# center_pcb.net
KiCad netlist of a schematic drawn in EAGLE
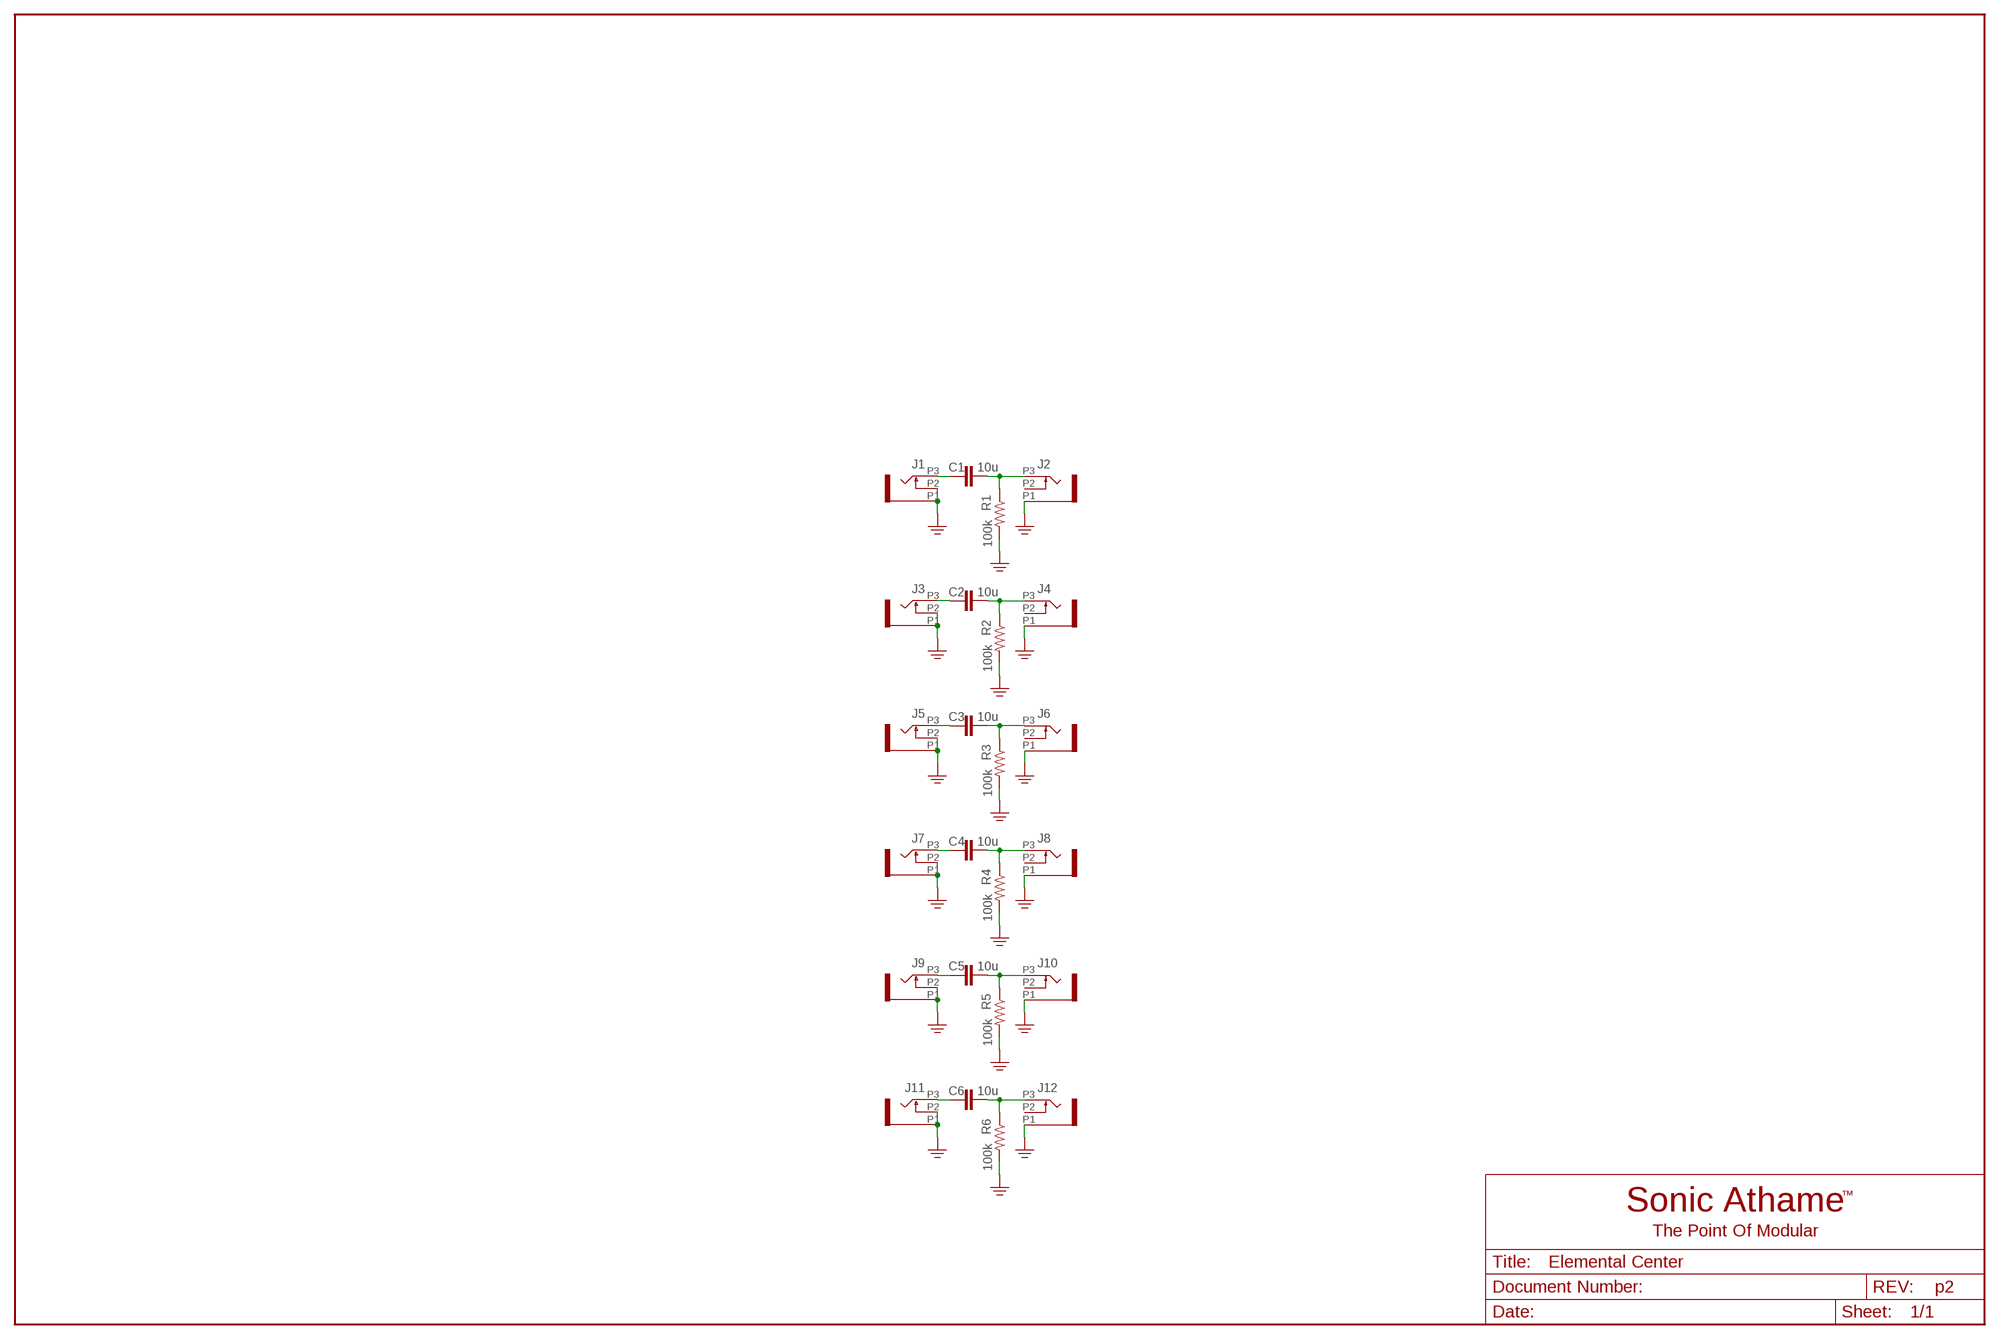
[diagram p0: schematic, sheet 1]

(export (version "E")
  (design (tool "Eeschema 10.0.6"))
  (components
    (comp (ref "C1")
      (value "10u")
      (footprint "eagle-import:C025-024X044")
      (libsource (lib "eagle-import") (part "CAP_NONPOL025-024X044"))
    )
    (comp (ref "C2")
      (value "10u")
      (footprint "eagle-import:C025-024X044")
      (libsource (lib "eagle-import") (part "CAP_NONPOL025-024X044"))
    )
    (comp (ref "C3")
      (value "10u")
      (footprint "eagle-import:C025-024X044")
      (libsource (lib "eagle-import") (part "CAP_NONPOL025-024X044"))
    )
    (comp (ref "C4")
      (value "10u")
      (footprint "eagle-import:C025-024X044")
      (libsource (lib "eagle-import") (part "CAP_NONPOL025-024X044"))
    )
    (comp (ref "C5")
      (value "10u")
      (footprint "eagle-import:C025-024X044")
      (libsource (lib "eagle-import") (part "CAP_NONPOL025-024X044"))
    )
    (comp (ref "C6")
      (value "10u")
      (footprint "eagle-import:C025-024X044")
      (libsource (lib "eagle-import") (part "CAP_NONPOL025-024X044"))
    )
    (comp (ref "J1")
      (value "WQP-PJ398SM6")
      (footprint "eagle-import:WQP_PJ_301M6")
      (libsource (lib "eagle-import") (part "WQP-PJ398SM6"))
    )
    (comp (ref "J2")
      (value "WQP-PJ398SM6")
      (footprint "eagle-import:WQP_PJ_301M6")
      (libsource (lib "eagle-import") (part "WQP-PJ398SM6"))
    )
    (comp (ref "J3")
      (value "WQP-PJ398SM6")
      (footprint "eagle-import:WQP_PJ_301M6")
      (libsource (lib "eagle-import") (part "WQP-PJ398SM6"))
    )
    (comp (ref "J4")
      (value "WQP-PJ398SM6")
      (footprint "eagle-import:WQP_PJ_301M6")
      (libsource (lib "eagle-import") (part "WQP-PJ398SM6"))
    )
    (comp (ref "J5")
      (value "WQP-PJ398SM6")
      (footprint "eagle-import:WQP_PJ_301M6")
      (libsource (lib "eagle-import") (part "WQP-PJ398SM6"))
    )
    (comp (ref "J6")
      (value "WQP-PJ398SM6")
      (footprint "eagle-import:WQP_PJ_301M6")
      (libsource (lib "eagle-import") (part "WQP-PJ398SM6"))
    )
    (comp (ref "J7")
      (value "WQP-PJ398SM6")
      (footprint "eagle-import:WQP_PJ_301M6")
      (libsource (lib "eagle-import") (part "WQP-PJ398SM6"))
    )
    (comp (ref "J8")
      (value "WQP-PJ398SM6")
      (footprint "eagle-import:WQP_PJ_301M6")
      (libsource (lib "eagle-import") (part "WQP-PJ398SM6"))
    )
    (comp (ref "J9")
      (value "WQP-PJ398SM6")
      (footprint "eagle-import:WQP_PJ_301M6")
      (libsource (lib "eagle-import") (part "WQP-PJ398SM6"))
    )
    (comp (ref "J10")
      (value "WQP-PJ398SM6")
      (footprint "eagle-import:WQP_PJ_301M6")
      (libsource (lib "eagle-import") (part "WQP-PJ398SM6"))
    )
    (comp (ref "J11")
      (value "WQP-PJ398SM6")
      (footprint "eagle-import:WQP_PJ_301M6")
      (libsource (lib "eagle-import") (part "WQP-PJ398SM6"))
    )
    (comp (ref "J12")
      (value "WQP-PJ398SM6")
      (footprint "eagle-import:WQP_PJ_301M6")
      (libsource (lib "eagle-import") (part "WQP-PJ398SM6"))
    )
    (comp (ref "R1")
      (value "100k")
      (footprint "eagle-import:0207_2V")
      (libsource (lib "eagle-import") (part "RESISTOR0207/2V"))
    )
    (comp (ref "R2")
      (value "100k")
      (footprint "eagle-import:0207_2V")
      (libsource (lib "eagle-import") (part "RESISTOR0207/2V"))
    )
    (comp (ref "R3")
      (value "100k")
      (footprint "eagle-import:0207_2V")
      (libsource (lib "eagle-import") (part "RESISTOR0207/2V"))
    )
    (comp (ref "R4")
      (value "100k")
      (footprint "eagle-import:0207_2V")
      (libsource (lib "eagle-import") (part "RESISTOR0207/2V"))
    )
    (comp (ref "R5")
      (value "100k")
      (footprint "eagle-import:0207_2V")
      (libsource (lib "eagle-import") (part "RESISTOR0207/2V"))
    )
    (comp (ref "R6")
      (value "100k")
      (footprint "eagle-import:0207_2V")
      (libsource (lib "eagle-import") (part "RESISTOR0207/2V"))
    )
  )
  (nets
    (net (code "1") (name "GND") (class "Default")
      (node (ref "J1") (pin "P1") (pinfunction "1_P1") (pintype "passive"))
      (node (ref "J1") (pin "P2") (pinfunction "2_P2") (pintype "passive"))
      (node (ref "J10") (pin "P1") (pinfunction "1_P1") (pintype "passive"))
      (node (ref "J11") (pin "P1") (pinfunction "1_P1") (pintype "passive"))
      (node (ref "J11") (pin "P2") (pinfunction "2_P2") (pintype "passive"))
      (node (ref "J12") (pin "P1") (pinfunction "1_P1") (pintype "passive"))
      (node (ref "J2") (pin "P1") (pinfunction "1_P1") (pintype "passive"))
      (node (ref "J3") (pin "P1") (pinfunction "1_P1") (pintype "passive"))
      (node (ref "J3") (pin "P2") (pinfunction "2_P2") (pintype "passive"))
      (node (ref "J4") (pin "P1") (pinfunction "1_P1") (pintype "passive"))
      (node (ref "J5") (pin "P1") (pinfunction "1_P1") (pintype "passive"))
      (node (ref "J5") (pin "P2") (pinfunction "2_P2") (pintype "passive"))
      (node (ref "J6") (pin "P1") (pinfunction "1_P1") (pintype "passive"))
      (node (ref "J7") (pin "P1") (pinfunction "1_P1") (pintype "passive"))
      (node (ref "J7") (pin "P2") (pinfunction "2_P2") (pintype "passive"))
      (node (ref "J8") (pin "P1") (pinfunction "1_P1") (pintype "passive"))
      (node (ref "J9") (pin "P1") (pinfunction "1_P1") (pintype "passive"))
      (node (ref "J9") (pin "P2") (pinfunction "2_P2") (pintype "passive"))
      (node (ref "R1") (pin "2") (pinfunction "2_2") (pintype "passive"))
      (node (ref "R2") (pin "2") (pinfunction "2_2") (pintype "passive"))
      (node (ref "R3") (pin "2") (pinfunction "2_2") (pintype "passive"))
      (node (ref "R4") (pin "2") (pinfunction "2_2") (pintype "passive"))
      (node (ref "R5") (pin "2") (pinfunction "2_2") (pintype "passive"))
      (node (ref "R6") (pin "2") (pinfunction "2_2") (pintype "passive"))
    )
    (net (code "2") (name "Net-(J1-3)") (class "Default")
      (node (ref "C1") (pin "1") (pinfunction "1_1") (pintype "passive"))
      (node (ref "J1") (pin "P3") (pinfunction "3_P3") (pintype "passive"))
    )
    (net (code "3") (name "Net-(J2-3)") (class "Default")
      (node (ref "C1") (pin "2") (pinfunction "2_2") (pintype "passive"))
      (node (ref "J2") (pin "P3") (pinfunction "3_P3") (pintype "passive"))
      (node (ref "R1") (pin "1") (pinfunction "1_1") (pintype "passive"))
    )
    (net (code "4") (name "Net-(J3-3)") (class "Default")
      (node (ref "C2") (pin "1") (pinfunction "1_1") (pintype "passive"))
      (node (ref "J3") (pin "P3") (pinfunction "3_P3") (pintype "passive"))
    )
    (net (code "5") (name "Net-(J4-3)") (class "Default")
      (node (ref "C2") (pin "2") (pinfunction "2_2") (pintype "passive"))
      (node (ref "J4") (pin "P3") (pinfunction "3_P3") (pintype "passive"))
      (node (ref "R2") (pin "1") (pinfunction "1_1") (pintype "passive"))
    )
    (net (code "6") (name "Net-(J5-3)") (class "Default")
      (node (ref "C3") (pin "1") (pinfunction "1_1") (pintype "passive"))
      (node (ref "J5") (pin "P3") (pinfunction "3_P3") (pintype "passive"))
    )
    (net (code "7") (name "Net-(J6-3)") (class "Default")
      (node (ref "C3") (pin "2") (pinfunction "2_2") (pintype "passive"))
      (node (ref "J6") (pin "P3") (pinfunction "3_P3") (pintype "passive"))
      (node (ref "R3") (pin "1") (pinfunction "1_1") (pintype "passive"))
    )
    (net (code "8") (name "Net-(J7-3)") (class "Default")
      (node (ref "C4") (pin "1") (pinfunction "1_1") (pintype "passive"))
      (node (ref "J7") (pin "P3") (pinfunction "3_P3") (pintype "passive"))
    )
    (net (code "9") (name "Net-(J8-3)") (class "Default")
      (node (ref "C4") (pin "2") (pinfunction "2_2") (pintype "passive"))
      (node (ref "J8") (pin "P3") (pinfunction "3_P3") (pintype "passive"))
      (node (ref "R4") (pin "1") (pinfunction "1_1") (pintype "passive"))
    )
    (net (code "10") (name "Net-(J9-3)") (class "Default")
      (node (ref "C5") (pin "1") (pinfunction "1_1") (pintype "passive"))
      (node (ref "J9") (pin "P3") (pinfunction "3_P3") (pintype "passive"))
    )
    (net (code "11") (name "Net-(J10-3)") (class "Default")
      (node (ref "C5") (pin "2") (pinfunction "2_2") (pintype "passive"))
      (node (ref "J10") (pin "P3") (pinfunction "3_P3") (pintype "passive"))
      (node (ref "R5") (pin "1") (pinfunction "1_1") (pintype "passive"))
    )
    (net (code "12") (name "Net-(J11-3)") (class "Default")
      (node (ref "C6") (pin "1") (pinfunction "1_1") (pintype "passive"))
      (node (ref "J11") (pin "P3") (pinfunction "3_P3") (pintype "passive"))
    )
    (net (code "13") (name "Net-(J12-3)") (class "Default")
      (node (ref "C6") (pin "2") (pinfunction "2_2") (pintype "passive"))
      (node (ref "J12") (pin "P3") (pinfunction "3_P3") (pintype "passive"))
      (node (ref "R6") (pin "1") (pinfunction "1_1") (pintype "passive"))
    )
    (net (code "14") (name "unconnected-(J2-2-PadP2)") (class "Default")
      (node (ref "J2") (pin "P2") (pinfunction "2_P2") (pintype "passive"))
    )
    (net (code "15") (name "unconnected-(J4-2-PadP2)") (class "Default")
      (node (ref "J4") (pin "P2") (pinfunction "2_P2") (pintype "passive"))
    )
    (net (code "16") (name "unconnected-(J6-2-PadP2)") (class "Default")
      (node (ref "J6") (pin "P2") (pinfunction "2_P2") (pintype "passive"))
    )
    (net (code "17") (name "unconnected-(J8-2-PadP2)") (class "Default")
      (node (ref "J8") (pin "P2") (pinfunction "2_P2") (pintype "passive"))
    )
    (net (code "18") (name "unconnected-(J10-2-PadP2)") (class "Default")
      (node (ref "J10") (pin "P2") (pinfunction "2_P2") (pintype "passive"))
    )
    (net (code "19") (name "unconnected-(J12-2-PadP2)") (class "Default")
      (node (ref "J12") (pin "P2") (pinfunction "2_P2") (pintype "passive"))
    )
  )
)
